# Auction_Multi_RevA_Final.net
KiCad netlist of a schematic drawn in EAGLE
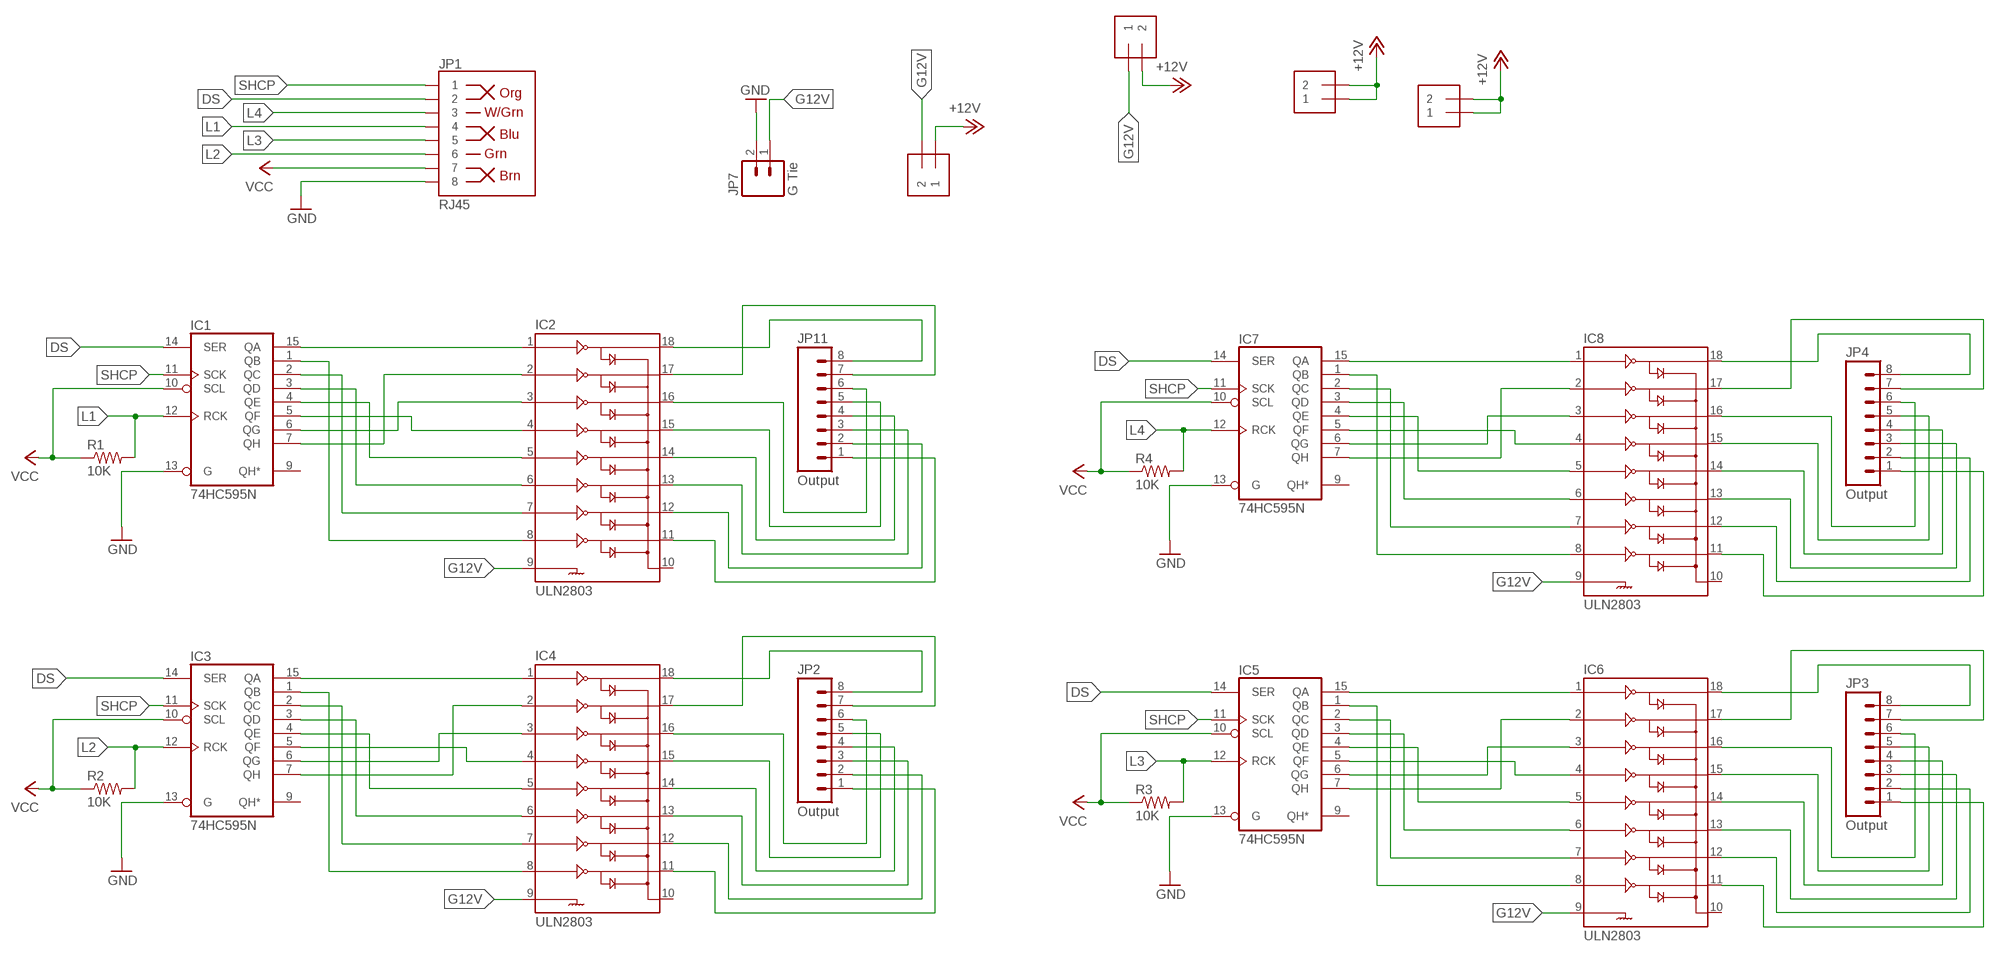
[diagram p0: schematic, sheet 1]

(export (version "E")
  (design (tool "Eeschema 10.0.6"))
  (components
    (comp (ref "IC1")
      (value "74HC595N")
      (footprint "eagle-import:DIL16")
      (fields (field (name "MF") "TEXAS INSTRUMENTS") (field (name "MPN") "SN74HC595N"))
      (libsource (lib "eagle-import") (part "74595NHC"))
    )
    (comp (ref "IC2")
      (value "ULN2803")
      (footprint "eagle-import:DIL18")
      (fields (field (name "MF") "Arrow Electronics") (field (name "MPN") "ULN2803A"))
      (libsource (lib "eagle-import") (part "ULN2803DIP"))
    )
    (comp (ref "IC3")
      (value "74HC595N")
      (footprint "eagle-import:DIL16")
      (fields (field (name "MF") "TEXAS INSTRUMENTS") (field (name "MPN") "SN74HC595N"))
      (libsource (lib "eagle-import") (part "74595NHC"))
    )
    (comp (ref "IC4")
      (value "ULN2803")
      (footprint "eagle-import:DIL18")
      (fields (field (name "MF") "Arrow Electronics") (field (name "MPN") "ULN2803A"))
      (libsource (lib "eagle-import") (part "ULN2803DIP"))
    )
    (comp (ref "IC5")
      (value "74HC595N")
      (footprint "eagle-import:DIL16")
      (fields (field (name "MF") "TEXAS INSTRUMENTS") (field (name "MPN") "SN74HC595N"))
      (libsource (lib "eagle-import") (part "74595NHC"))
    )
    (comp (ref "IC6")
      (value "ULN2803")
      (footprint "eagle-import:DIL18")
      (fields (field (name "MF") "Arrow Electronics") (field (name "MPN") "ULN2803A"))
      (libsource (lib "eagle-import") (part "ULN2803DIP"))
    )
    (comp (ref "IC7")
      (value "74HC595N")
      (footprint "eagle-import:DIL16")
      (fields (field (name "MF") "TEXAS INSTRUMENTS") (field (name "MPN") "SN74HC595N"))
      (libsource (lib "eagle-import") (part "74595NHC"))
    )
    (comp (ref "IC8")
      (value "ULN2803")
      (footprint "eagle-import:DIL18")
      (fields (field (name "MF") "Arrow Electronics") (field (name "MPN") "ULN2803A"))
      (libsource (lib "eagle-import") (part "ULN2803DIP"))
    )
    (comp (ref "JP1")
      (value "RJ45")
      (footprint "eagle-import:RJ45-8")
      (fields (field (name "MPN") "54602-908LF"))
      (libsource (lib "eagle-import") (part "RJ45-8PTH"))
    )
    (comp (ref "JP2")
      (value "Output")
      (footprint "eagle-import:SCREWTERMINAL-3.5MM-8")
      (fields (field (name "MPN") "20020327-C081B01LF"))
      (libsource (lib "eagle-import") (part "M083.5MM-8"))
    )
    (comp (ref "JP3")
      (value "Output")
      (footprint "eagle-import:SCREWTERMINAL-3.5MM-8")
      (fields (field (name "MPN") "20020327-C081B01LF"))
      (libsource (lib "eagle-import") (part "M083.5MM-8"))
    )
    (comp (ref "JP4")
      (value "Output")
      (footprint "eagle-import:SCREWTERMINAL-3.5MM-8")
      (fields (field (name "MPN") "20020327-C081B01LF"))
      (libsource (lib "eagle-import") (part "M083.5MM-8"))
    )
    (comp (ref "JP5")
      (value "1X2-3.5MM")
      (footprint "eagle-import:1X2-3.5MM")
      (fields (field (name "MPN") "1776275-2"))
      (libsource (lib "eagle-import") (part "1X2-3.5MM"))
    )
    (comp (ref "JP7")
      (value "G Tie")
      (footprint "eagle-import:1X02")
      (fields (field (name "MPN") "2211S-02G"))
      (libsource (lib "eagle-import") (part "M02PTH"))
    )
    (comp (ref "JP8")
      (value "1X2-3.5MM")
      (footprint "eagle-import:1X2-3.5MM")
      (fields (field (name "MPN") "1776275-2"))
      (libsource (lib "eagle-import") (part "1X2-3.5MM"))
    )
    (comp (ref "JP9")
      (value "1X2-3.5MM")
      (footprint "eagle-import:1X2-3.5MM")
      (fields (field (name "MPN") "1776275-2"))
      (libsource (lib "eagle-import") (part "1X2-3.5MM"))
    )
    (comp (ref "JP10")
      (value "1X2-3.5MM")
      (footprint "eagle-import:1X2-3.5MM")
      (fields (field (name "MPN") "1776275-2"))
      (libsource (lib "eagle-import") (part "1X2-3.5MM"))
    )
    (comp (ref "JP11")
      (value "Output")
      (footprint "eagle-import:SCREWTERMINAL-3.5MM-8")
      (fields (field (name "MPN") "20020327-C081B01LF"))
      (libsource (lib "eagle-import") (part "M083.5MM-8"))
    )
    (comp (ref "R1")
      (value "10K")
      (footprint "eagle-import:AXIAL-0.3EZ")
      (fields (field (name "MF") "FARNELL") (field (name "MPN") "MCF 0.25W 10K"))
      (libsource (lib "eagle-import") (part "RESISTOREZ"))
    )
    (comp (ref "R2")
      (value "10K")
      (footprint "eagle-import:AXIAL-0.3EZ")
      (fields (field (name "MF") "FARNELL") (field (name "MPN") "MCF 0.25W 10K"))
      (libsource (lib "eagle-import") (part "RESISTOREZ"))
    )
    (comp (ref "R3")
      (value "10K")
      (footprint "eagle-import:AXIAL-0.3EZ")
      (fields (field (name "MF") "FARNELL") (field (name "MPN") "MCF 0.25W 10K"))
      (libsource (lib "eagle-import") (part "RESISTOREZ"))
    )
    (comp (ref "R4")
      (value "10K")
      (footprint "eagle-import:AXIAL-0.3EZ")
      (fields (field (name "MF") "FARNELL") (field (name "MPN") "MCF 0.25W 10K"))
      (libsource (lib "eagle-import") (part "RESISTOREZ"))
    )
  )
  (nets
    (net (code "1") (name "+12V") (class "Default")
      (node (ref "JP10") (pin "1") (pinfunction "1_1") (pintype "passive"))
      (node (ref "JP10") (pin "2") (pinfunction "2_2") (pintype "passive"))
      (node (ref "JP5") (pin "1") (pinfunction "1_1") (pintype "passive"))
      (node (ref "JP5") (pin "2") (pinfunction "2_2") (pintype "passive"))
      (node (ref "JP8") (pin "1") (pinfunction "1_1") (pintype "passive"))
      (node (ref "JP9") (pin "2") (pinfunction "2_2") (pintype "passive"))
    )
    (net (code "2") (name "DS") (class "Default")
      (node (ref "IC1") (pin "14") (pinfunction "SER_14") (pintype "input"))
      (node (ref "IC3") (pin "14") (pinfunction "SER_14") (pintype "input"))
      (node (ref "IC5") (pin "14") (pinfunction "SER_14") (pintype "input"))
      (node (ref "IC7") (pin "14") (pinfunction "SER_14") (pintype "input"))
      (node (ref "JP1") (pin "2") (pinfunction "2_2") (pintype "bidirectional"))
    )
    (net (code "3") (name "G12V") (class "Default")
      (node (ref "IC2") (pin "9") (pinfunction "9_9") (pintype "bidirectional"))
      (node (ref "IC4") (pin "9") (pinfunction "9_9") (pintype "bidirectional"))
      (node (ref "IC6") (pin "9") (pinfunction "9_9") (pintype "bidirectional"))
      (node (ref "IC8") (pin "9") (pinfunction "9_9") (pintype "bidirectional"))
      (node (ref "JP7") (pin "1") (pinfunction "1_1") (pintype "passive"))
      (node (ref "JP8") (pin "2") (pinfunction "2_2") (pintype "passive"))
      (node (ref "JP9") (pin "1") (pinfunction "1_1") (pintype "passive"))
    )
    (net (code "4") (name "GND") (class "Default")
      (node (ref "IC1") (pin "13") (pinfunction "G_13") (pintype "input"))
      (node (ref "IC3") (pin "13") (pinfunction "G_13") (pintype "input"))
      (node (ref "IC5") (pin "13") (pinfunction "G_13") (pintype "input"))
      (node (ref "IC7") (pin "13") (pinfunction "G_13") (pintype "input"))
      (node (ref "JP1") (pin "8") (pinfunction "8_8") (pintype "bidirectional"))
      (node (ref "JP7") (pin "2") (pinfunction "2_2") (pintype "passive"))
    )
    (net (code "5") (name "L1") (class "Default")
      (node (ref "IC1") (pin "12") (pinfunction "RCK_12") (pintype "input"))
      (node (ref "JP1") (pin "4") (pinfunction "4_4") (pintype "bidirectional"))
      (node (ref "R1") (pin "P$2") (pinfunction "2_P$2") (pintype "passive"))
    )
    (net (code "6") (name "L2") (class "Default")
      (node (ref "IC3") (pin "12") (pinfunction "RCK_12") (pintype "input"))
      (node (ref "JP1") (pin "6") (pinfunction "6_6") (pintype "bidirectional"))
      (node (ref "R2") (pin "P$2") (pinfunction "2_P$2") (pintype "passive"))
    )
    (net (code "7") (name "L3") (class "Default")
      (node (ref "IC5") (pin "12") (pinfunction "RCK_12") (pintype "input"))
      (node (ref "JP1") (pin "5") (pinfunction "5_5") (pintype "bidirectional"))
      (node (ref "R3") (pin "P$2") (pinfunction "2_P$2") (pintype "passive"))
    )
    (net (code "8") (name "L4") (class "Default")
      (node (ref "IC7") (pin "12") (pinfunction "RCK_12") (pintype "input"))
      (node (ref "JP1") (pin "3") (pinfunction "3_3") (pintype "bidirectional"))
      (node (ref "R4") (pin "P$2") (pinfunction "2_P$2") (pintype "passive"))
    )
    (net (code "9") (name "Net-(IC1A-QA)") (class "Default")
      (node (ref "IC1") (pin "15") (pinfunction "QA_15") (pintype "tri_state"))
      (node (ref "IC2") (pin "1") (pinfunction "1_1") (pintype "bidirectional"))
    )
    (net (code "10") (name "Net-(IC1A-QB)") (class "Default")
      (node (ref "IC1") (pin "1") (pinfunction "QB_1") (pintype "tri_state"))
      (node (ref "IC2") (pin "8") (pinfunction "8_8") (pintype "bidirectional"))
    )
    (net (code "11") (name "Net-(IC1A-QC)") (class "Default")
      (node (ref "IC1") (pin "2") (pinfunction "QC_2") (pintype "tri_state"))
      (node (ref "IC2") (pin "7") (pinfunction "7_7") (pintype "bidirectional"))
    )
    (net (code "12") (name "Net-(IC1A-QD)") (class "Default")
      (node (ref "IC1") (pin "3") (pinfunction "QD_3") (pintype "tri_state"))
      (node (ref "IC2") (pin "6") (pinfunction "6_6") (pintype "bidirectional"))
    )
    (net (code "13") (name "Net-(IC1A-QE)") (class "Default")
      (node (ref "IC1") (pin "4") (pinfunction "QE_4") (pintype "tri_state"))
      (node (ref "IC2") (pin "5") (pinfunction "5_5") (pintype "bidirectional"))
    )
    (net (code "14") (name "Net-(IC1A-QF)") (class "Default")
      (node (ref "IC1") (pin "5") (pinfunction "QF_5") (pintype "tri_state"))
      (node (ref "IC2") (pin "4") (pinfunction "4_4") (pintype "bidirectional"))
    )
    (net (code "15") (name "Net-(IC1A-QG)") (class "Default")
      (node (ref "IC1") (pin "6") (pinfunction "QG_6") (pintype "tri_state"))
      (node (ref "IC2") (pin "3") (pinfunction "3_3") (pintype "bidirectional"))
    )
    (net (code "16") (name "Net-(IC1A-QH)") (class "Default")
      (node (ref "IC1") (pin "7") (pinfunction "QH_7") (pintype "tri_state"))
      (node (ref "IC2") (pin "2") (pinfunction "2_2") (pintype "bidirectional"))
    )
    (net (code "17") (name "Net-(IC2-Pad11)") (class "Default")
      (node (ref "IC2") (pin "11") (pinfunction "11_11") (pintype "bidirectional"))
      (node (ref "JP11") (pin "1") (pinfunction "1_1") (pintype "passive"))
    )
    (net (code "18") (name "Net-(IC2-Pad12)") (class "Default")
      (node (ref "IC2") (pin "12") (pinfunction "12_12") (pintype "bidirectional"))
      (node (ref "JP11") (pin "2") (pinfunction "2_2") (pintype "passive"))
    )
    (net (code "19") (name "Net-(IC2-Pad13)") (class "Default")
      (node (ref "IC2") (pin "13") (pinfunction "13_13") (pintype "bidirectional"))
      (node (ref "JP11") (pin "3") (pinfunction "3_3") (pintype "passive"))
    )
    (net (code "20") (name "Net-(IC2-Pad14)") (class "Default")
      (node (ref "IC2") (pin "14") (pinfunction "14_14") (pintype "bidirectional"))
      (node (ref "JP11") (pin "4") (pinfunction "4_4") (pintype "passive"))
    )
    (net (code "21") (name "Net-(IC2-Pad15)") (class "Default")
      (node (ref "IC2") (pin "15") (pinfunction "15_15") (pintype "bidirectional"))
      (node (ref "JP11") (pin "5") (pinfunction "5_5") (pintype "passive"))
    )
    (net (code "22") (name "Net-(IC2-Pad16)") (class "Default")
      (node (ref "IC2") (pin "16") (pinfunction "16_16") (pintype "bidirectional"))
      (node (ref "JP11") (pin "6") (pinfunction "6_6") (pintype "passive"))
    )
    (net (code "23") (name "Net-(IC2-Pad17)") (class "Default")
      (node (ref "IC2") (pin "17") (pinfunction "17_17") (pintype "bidirectional"))
      (node (ref "JP11") (pin "7") (pinfunction "7_7") (pintype "passive"))
    )
    (net (code "24") (name "Net-(IC2-Pad18)") (class "Default")
      (node (ref "IC2") (pin "18") (pinfunction "18_18") (pintype "bidirectional"))
      (node (ref "JP11") (pin "8") (pinfunction "8_8") (pintype "passive"))
    )
    (net (code "25") (name "Net-(IC3A-QA)") (class "Default")
      (node (ref "IC3") (pin "15") (pinfunction "QA_15") (pintype "tri_state"))
      (node (ref "IC4") (pin "1") (pinfunction "1_1") (pintype "bidirectional"))
    )
    (net (code "26") (name "Net-(IC3A-QB)") (class "Default")
      (node (ref "IC3") (pin "1") (pinfunction "QB_1") (pintype "tri_state"))
      (node (ref "IC4") (pin "8") (pinfunction "8_8") (pintype "bidirectional"))
    )
    (net (code "27") (name "Net-(IC3A-QC)") (class "Default")
      (node (ref "IC3") (pin "2") (pinfunction "QC_2") (pintype "tri_state"))
      (node (ref "IC4") (pin "7") (pinfunction "7_7") (pintype "bidirectional"))
    )
    (net (code "28") (name "Net-(IC3A-QD)") (class "Default")
      (node (ref "IC3") (pin "3") (pinfunction "QD_3") (pintype "tri_state"))
      (node (ref "IC4") (pin "6") (pinfunction "6_6") (pintype "bidirectional"))
    )
    (net (code "29") (name "Net-(IC3A-QE)") (class "Default")
      (node (ref "IC3") (pin "4") (pinfunction "QE_4") (pintype "tri_state"))
      (node (ref "IC4") (pin "5") (pinfunction "5_5") (pintype "bidirectional"))
    )
    (net (code "30") (name "Net-(IC3A-QF)") (class "Default")
      (node (ref "IC3") (pin "5") (pinfunction "QF_5") (pintype "tri_state"))
      (node (ref "IC4") (pin "4") (pinfunction "4_4") (pintype "bidirectional"))
    )
    (net (code "31") (name "Net-(IC3A-QG)") (class "Default")
      (node (ref "IC3") (pin "6") (pinfunction "QG_6") (pintype "tri_state"))
      (node (ref "IC4") (pin "3") (pinfunction "3_3") (pintype "bidirectional"))
    )
    (net (code "32") (name "Net-(IC3A-QH)") (class "Default")
      (node (ref "IC3") (pin "7") (pinfunction "QH_7") (pintype "tri_state"))
      (node (ref "IC4") (pin "2") (pinfunction "2_2") (pintype "bidirectional"))
    )
    (net (code "33") (name "Net-(IC4-Pad11)") (class "Default")
      (node (ref "IC4") (pin "11") (pinfunction "11_11") (pintype "bidirectional"))
      (node (ref "JP2") (pin "1") (pinfunction "1_1") (pintype "passive"))
    )
    (net (code "34") (name "Net-(IC4-Pad12)") (class "Default")
      (node (ref "IC4") (pin "12") (pinfunction "12_12") (pintype "bidirectional"))
      (node (ref "JP2") (pin "2") (pinfunction "2_2") (pintype "passive"))
    )
    (net (code "35") (name "Net-(IC4-Pad13)") (class "Default")
      (node (ref "IC4") (pin "13") (pinfunction "13_13") (pintype "bidirectional"))
      (node (ref "JP2") (pin "3") (pinfunction "3_3") (pintype "passive"))
    )
    (net (code "36") (name "Net-(IC4-Pad14)") (class "Default")
      (node (ref "IC4") (pin "14") (pinfunction "14_14") (pintype "bidirectional"))
      (node (ref "JP2") (pin "4") (pinfunction "4_4") (pintype "passive"))
    )
    (net (code "37") (name "Net-(IC4-Pad15)") (class "Default")
      (node (ref "IC4") (pin "15") (pinfunction "15_15") (pintype "bidirectional"))
      (node (ref "JP2") (pin "5") (pinfunction "5_5") (pintype "passive"))
    )
    (net (code "38") (name "Net-(IC4-Pad16)") (class "Default")
      (node (ref "IC4") (pin "16") (pinfunction "16_16") (pintype "bidirectional"))
      (node (ref "JP2") (pin "6") (pinfunction "6_6") (pintype "passive"))
    )
    (net (code "39") (name "Net-(IC4-Pad17)") (class "Default")
      (node (ref "IC4") (pin "17") (pinfunction "17_17") (pintype "bidirectional"))
      (node (ref "JP2") (pin "7") (pinfunction "7_7") (pintype "passive"))
    )
    (net (code "40") (name "Net-(IC4-Pad18)") (class "Default")
      (node (ref "IC4") (pin "18") (pinfunction "18_18") (pintype "bidirectional"))
      (node (ref "JP2") (pin "8") (pinfunction "8_8") (pintype "passive"))
    )
    (net (code "41") (name "Net-(IC5A-QA)") (class "Default")
      (node (ref "IC5") (pin "15") (pinfunction "QA_15") (pintype "tri_state"))
      (node (ref "IC6") (pin "1") (pinfunction "1_1") (pintype "bidirectional"))
    )
    (net (code "42") (name "Net-(IC5A-QB)") (class "Default")
      (node (ref "IC5") (pin "1") (pinfunction "QB_1") (pintype "tri_state"))
      (node (ref "IC6") (pin "8") (pinfunction "8_8") (pintype "bidirectional"))
    )
    (net (code "43") (name "Net-(IC5A-QC)") (class "Default")
      (node (ref "IC5") (pin "2") (pinfunction "QC_2") (pintype "tri_state"))
      (node (ref "IC6") (pin "7") (pinfunction "7_7") (pintype "bidirectional"))
    )
    (net (code "44") (name "Net-(IC5A-QD)") (class "Default")
      (node (ref "IC5") (pin "3") (pinfunction "QD_3") (pintype "tri_state"))
      (node (ref "IC6") (pin "6") (pinfunction "6_6") (pintype "bidirectional"))
    )
    (net (code "45") (name "Net-(IC5A-QE)") (class "Default")
      (node (ref "IC5") (pin "4") (pinfunction "QE_4") (pintype "tri_state"))
      (node (ref "IC6") (pin "5") (pinfunction "5_5") (pintype "bidirectional"))
    )
    (net (code "46") (name "Net-(IC5A-QF)") (class "Default")
      (node (ref "IC5") (pin "5") (pinfunction "QF_5") (pintype "tri_state"))
      (node (ref "IC6") (pin "4") (pinfunction "4_4") (pintype "bidirectional"))
    )
    (net (code "47") (name "Net-(IC5A-QG)") (class "Default")
      (node (ref "IC5") (pin "6") (pinfunction "QG_6") (pintype "tri_state"))
      (node (ref "IC6") (pin "3") (pinfunction "3_3") (pintype "bidirectional"))
    )
    (net (code "48") (name "Net-(IC5A-QH)") (class "Default")
      (node (ref "IC5") (pin "7") (pinfunction "QH_7") (pintype "tri_state"))
      (node (ref "IC6") (pin "2") (pinfunction "2_2") (pintype "bidirectional"))
    )
    (net (code "49") (name "Net-(IC6-Pad11)") (class "Default")
      (node (ref "IC6") (pin "11") (pinfunction "11_11") (pintype "bidirectional"))
      (node (ref "JP3") (pin "1") (pinfunction "1_1") (pintype "passive"))
    )
    (net (code "50") (name "Net-(IC6-Pad12)") (class "Default")
      (node (ref "IC6") (pin "12") (pinfunction "12_12") (pintype "bidirectional"))
      (node (ref "JP3") (pin "2") (pinfunction "2_2") (pintype "passive"))
    )
    (net (code "51") (name "Net-(IC6-Pad13)") (class "Default")
      (node (ref "IC6") (pin "13") (pinfunction "13_13") (pintype "bidirectional"))
      (node (ref "JP3") (pin "3") (pinfunction "3_3") (pintype "passive"))
    )
    (net (code "52") (name "Net-(IC6-Pad14)") (class "Default")
      (node (ref "IC6") (pin "14") (pinfunction "14_14") (pintype "bidirectional"))
      (node (ref "JP3") (pin "4") (pinfunction "4_4") (pintype "passive"))
    )
    (net (code "53") (name "Net-(IC6-Pad15)") (class "Default")
      (node (ref "IC6") (pin "15") (pinfunction "15_15") (pintype "bidirectional"))
      (node (ref "JP3") (pin "5") (pinfunction "5_5") (pintype "passive"))
    )
    (net (code "54") (name "Net-(IC6-Pad16)") (class "Default")
      (node (ref "IC6") (pin "16") (pinfunction "16_16") (pintype "bidirectional"))
      (node (ref "JP3") (pin "6") (pinfunction "6_6") (pintype "passive"))
    )
    (net (code "55") (name "Net-(IC6-Pad17)") (class "Default")
      (node (ref "IC6") (pin "17") (pinfunction "17_17") (pintype "bidirectional"))
      (node (ref "JP3") (pin "7") (pinfunction "7_7") (pintype "passive"))
    )
    (net (code "56") (name "Net-(IC6-Pad18)") (class "Default")
      (node (ref "IC6") (pin "18") (pinfunction "18_18") (pintype "bidirectional"))
      (node (ref "JP3") (pin "8") (pinfunction "8_8") (pintype "passive"))
    )
    (net (code "57") (name "Net-(IC7A-QA)") (class "Default")
      (node (ref "IC7") (pin "15") (pinfunction "QA_15") (pintype "tri_state"))
      (node (ref "IC8") (pin "1") (pinfunction "1_1") (pintype "bidirectional"))
    )
    (net (code "58") (name "Net-(IC7A-QB)") (class "Default")
      (node (ref "IC7") (pin "1") (pinfunction "QB_1") (pintype "tri_state"))
      (node (ref "IC8") (pin "8") (pinfunction "8_8") (pintype "bidirectional"))
    )
    (net (code "59") (name "Net-(IC7A-QC)") (class "Default")
      (node (ref "IC7") (pin "2") (pinfunction "QC_2") (pintype "tri_state"))
      (node (ref "IC8") (pin "7") (pinfunction "7_7") (pintype "bidirectional"))
    )
    (net (code "60") (name "Net-(IC7A-QD)") (class "Default")
      (node (ref "IC7") (pin "3") (pinfunction "QD_3") (pintype "tri_state"))
      (node (ref "IC8") (pin "6") (pinfunction "6_6") (pintype "bidirectional"))
    )
    (net (code "61") (name "Net-(IC7A-QE)") (class "Default")
      (node (ref "IC7") (pin "4") (pinfunction "QE_4") (pintype "tri_state"))
      (node (ref "IC8") (pin "5") (pinfunction "5_5") (pintype "bidirectional"))
    )
    (net (code "62") (name "Net-(IC7A-QF)") (class "Default")
      (node (ref "IC7") (pin "5") (pinfunction "QF_5") (pintype "tri_state"))
      (node (ref "IC8") (pin "4") (pinfunction "4_4") (pintype "bidirectional"))
    )
    (net (code "63") (name "Net-(IC7A-QG)") (class "Default")
      (node (ref "IC7") (pin "6") (pinfunction "QG_6") (pintype "tri_state"))
      (node (ref "IC8") (pin "3") (pinfunction "3_3") (pintype "bidirectional"))
    )
    (net (code "64") (name "Net-(IC7A-QH)") (class "Default")
      (node (ref "IC7") (pin "7") (pinfunction "QH_7") (pintype "tri_state"))
      (node (ref "IC8") (pin "2") (pinfunction "2_2") (pintype "bidirectional"))
    )
    (net (code "65") (name "Net-(IC8-Pad11)") (class "Default")
      (node (ref "IC8") (pin "11") (pinfunction "11_11") (pintype "bidirectional"))
      (node (ref "JP4") (pin "1") (pinfunction "1_1") (pintype "passive"))
    )
    (net (code "66") (name "Net-(IC8-Pad12)") (class "Default")
      (node (ref "IC8") (pin "12") (pinfunction "12_12") (pintype "bidirectional"))
      (node (ref "JP4") (pin "2") (pinfunction "2_2") (pintype "passive"))
    )
    (net (code "67") (name "Net-(IC8-Pad13)") (class "Default")
      (node (ref "IC8") (pin "13") (pinfunction "13_13") (pintype "bidirectional"))
      (node (ref "JP4") (pin "3") (pinfunction "3_3") (pintype "passive"))
    )
    (net (code "68") (name "Net-(IC8-Pad14)") (class "Default")
      (node (ref "IC8") (pin "14") (pinfunction "14_14") (pintype "bidirectional"))
      (node (ref "JP4") (pin "4") (pinfunction "4_4") (pintype "passive"))
    )
    (net (code "69") (name "Net-(IC8-Pad15)") (class "Default")
      (node (ref "IC8") (pin "15") (pinfunction "15_15") (pintype "bidirectional"))
      (node (ref "JP4") (pin "5") (pinfunction "5_5") (pintype "passive"))
    )
    (net (code "70") (name "Net-(IC8-Pad16)") (class "Default")
      (node (ref "IC8") (pin "16") (pinfunction "16_16") (pintype "bidirectional"))
      (node (ref "JP4") (pin "6") (pinfunction "6_6") (pintype "passive"))
    )
    (net (code "71") (name "Net-(IC8-Pad17)") (class "Default")
      (node (ref "IC8") (pin "17") (pinfunction "17_17") (pintype "bidirectional"))
      (node (ref "JP4") (pin "7") (pinfunction "7_7") (pintype "passive"))
    )
    (net (code "72") (name "Net-(IC8-Pad18)") (class "Default")
      (node (ref "IC8") (pin "18") (pinfunction "18_18") (pintype "bidirectional"))
      (node (ref "JP4") (pin "8") (pinfunction "8_8") (pintype "passive"))
    )
    (net (code "73") (name "SHCP") (class "Default")
      (node (ref "IC1") (pin "11") (pinfunction "SCK_11") (pintype "input"))
      (node (ref "IC3") (pin "11") (pinfunction "SCK_11") (pintype "input"))
      (node (ref "IC5") (pin "11") (pinfunction "SCK_11") (pintype "input"))
      (node (ref "IC7") (pin "11") (pinfunction "SCK_11") (pintype "input"))
      (node (ref "JP1") (pin "1") (pinfunction "1_1") (pintype "bidirectional"))
    )
    (net (code "74") (name "VCC") (class "Default")
      (node (ref "IC1") (pin "10") (pinfunction "SCL_10") (pintype "input"))
      (node (ref "IC3") (pin "10") (pinfunction "SCL_10") (pintype "input"))
      (node (ref "IC5") (pin "10") (pinfunction "SCL_10") (pintype "input"))
      (node (ref "IC7") (pin "10") (pinfunction "SCL_10") (pintype "input"))
      (node (ref "JP1") (pin "7") (pinfunction "7_7") (pintype "bidirectional"))
      (node (ref "R1") (pin "P$1") (pinfunction "1_P$1") (pintype "passive"))
      (node (ref "R2") (pin "P$1") (pinfunction "1_P$1") (pintype "passive"))
      (node (ref "R3") (pin "P$1") (pinfunction "1_P$1") (pintype "passive"))
      (node (ref "R4") (pin "P$1") (pinfunction "1_P$1") (pintype "passive"))
    )
    (net (code "75") (name "unconnected-(IC1A-QH*-Pad9)") (class "Default")
      (node (ref "IC1") (pin "9") (pinfunction "QH*_9") (pintype "tri_state"))
    )
    (net (code "76") (name "unconnected-(IC2-Pad10)") (class "Default")
      (node (ref "IC2") (pin "10") (pinfunction "10_10") (pintype "bidirectional"))
    )
    (net (code "77") (name "unconnected-(IC3A-QH*-Pad9)") (class "Default")
      (node (ref "IC3") (pin "9") (pinfunction "QH*_9") (pintype "tri_state"))
    )
    (net (code "78") (name "unconnected-(IC4-Pad10)") (class "Default")
      (node (ref "IC4") (pin "10") (pinfunction "10_10") (pintype "bidirectional"))
    )
    (net (code "79") (name "unconnected-(IC5A-QH*-Pad9)") (class "Default")
      (node (ref "IC5") (pin "9") (pinfunction "QH*_9") (pintype "tri_state"))
    )
    (net (code "80") (name "unconnected-(IC6-Pad10)") (class "Default")
      (node (ref "IC6") (pin "10") (pinfunction "10_10") (pintype "bidirectional"))
    )
    (net (code "81") (name "unconnected-(IC7A-QH*-Pad9)") (class "Default")
      (node (ref "IC7") (pin "9") (pinfunction "QH*_9") (pintype "tri_state"))
    )
    (net (code "82") (name "unconnected-(IC8-Pad10)") (class "Default")
      (node (ref "IC8") (pin "10") (pinfunction "10_10") (pintype "bidirectional"))
    )
  )
)
